# mirobot_main.net
KiCad netlist of a schematic drawn in EAGLE
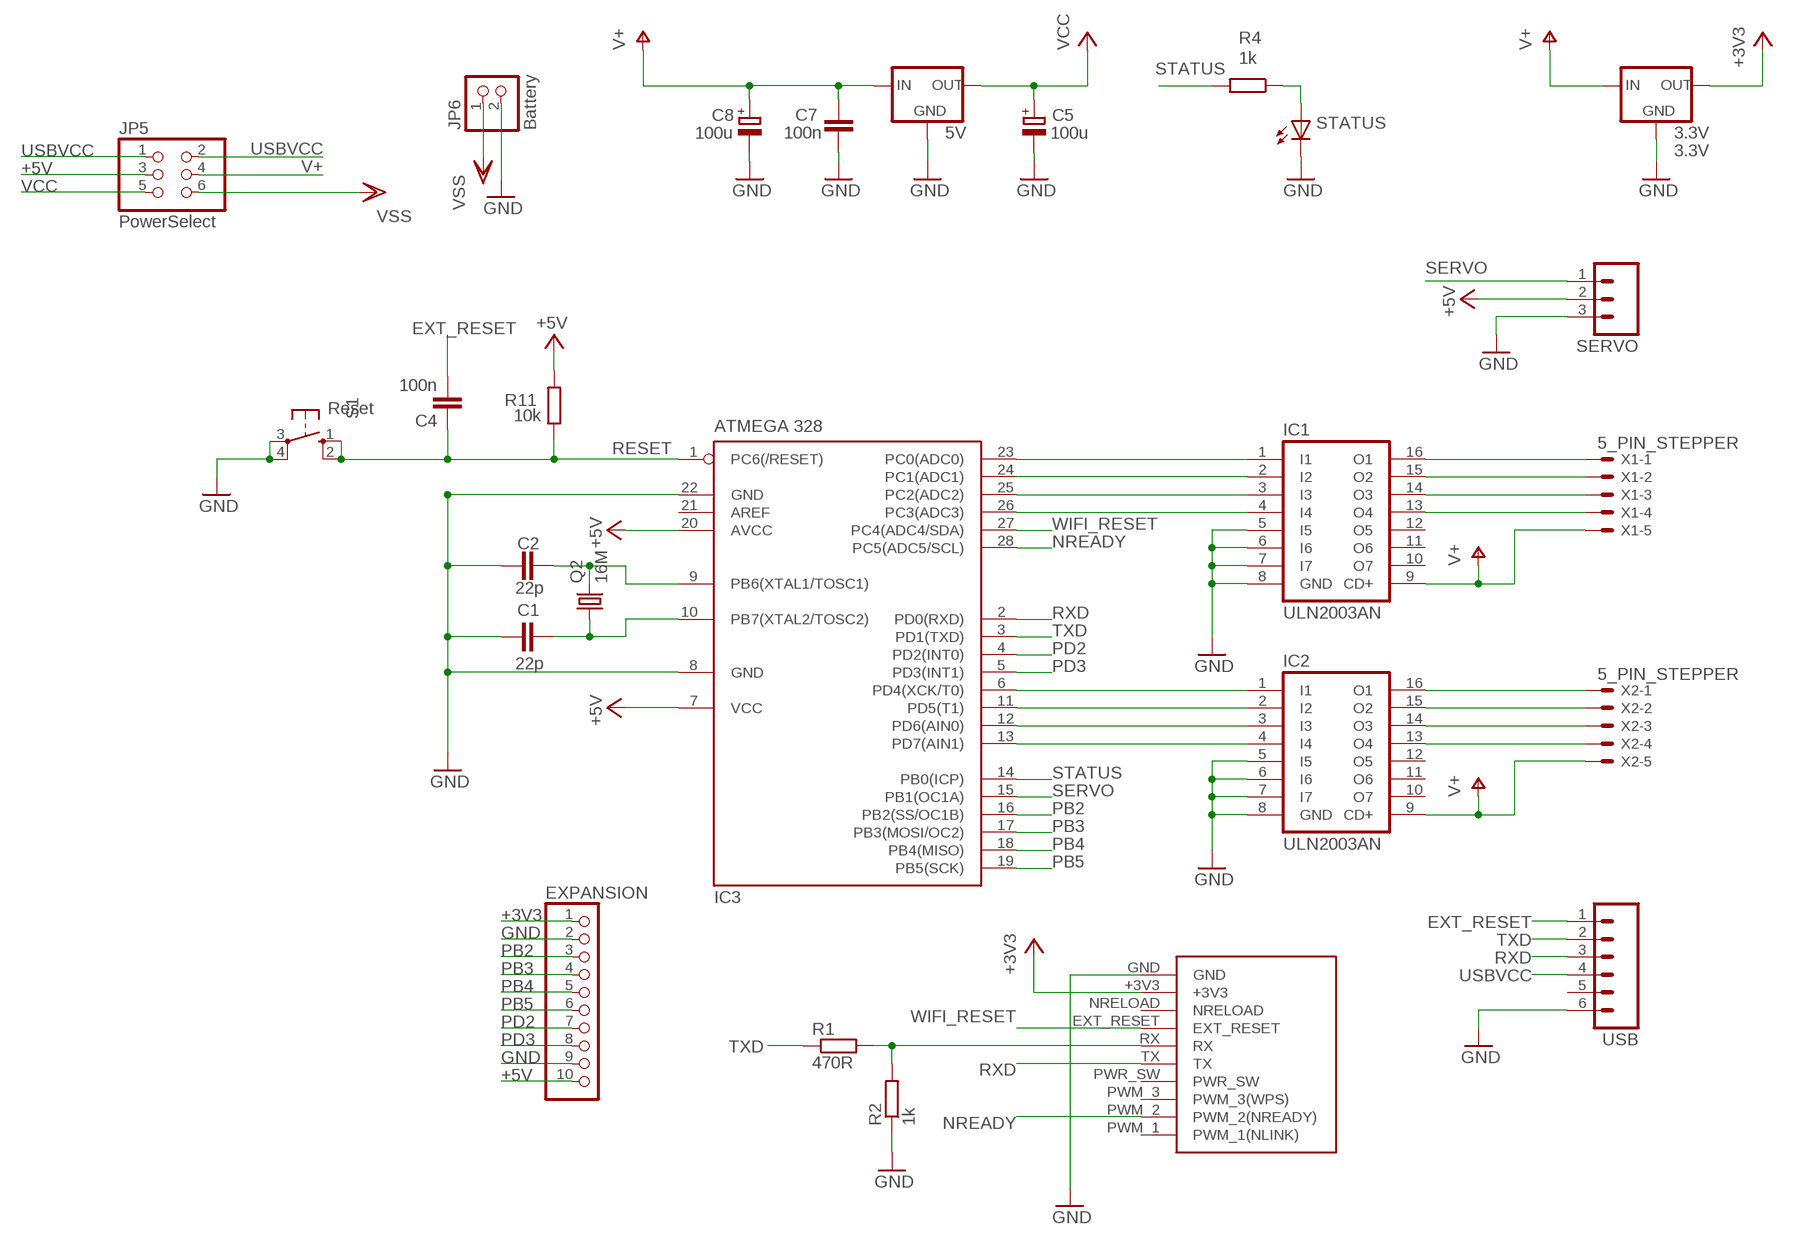
[diagram p0: schematic, sheet 1]

(export (version "E")
  (design (tool "Eeschema 10.0.6"))
  (components
    (comp (ref "3.3V")
      (value "3.3V")
      (footprint "eagle-import:78LXX")
      (libsource (lib "eagle-import") (part "78LXX"))
    )
    (comp (ref "5V")
      (value "78MXXS")
      (footprint "eagle-import:78MXXS")
      (libsource (lib "eagle-import") (part "78MXXS"))
    )
    (comp (ref "C1")
      (value "22p")
      (footprint "eagle-import:C025-024X044")
      (libsource (lib "eagle-import") (part "C-EU025-024X044"))
    )
    (comp (ref "C2")
      (value "22p")
      (footprint "eagle-import:C025-024X044")
      (libsource (lib "eagle-import") (part "C-EU025-024X044"))
    )
    (comp (ref "C4")
      (value "100n")
      (footprint "eagle-import:C050-025X075")
      (libsource (lib "eagle-import") (part "C-EU050-025X075"))
    )
    (comp (ref "C5")
      (value "100u")
      (footprint "eagle-import:E2-5")
      (libsource (lib "eagle-import") (part "CPOL-EUE2-5"))
    )
    (comp (ref "C7")
      (value "100n")
      (footprint "eagle-import:C050-025X075")
      (libsource (lib "eagle-import") (part "C-EU050-025X075"))
    )
    (comp (ref "C8")
      (value "100u")
      (footprint "eagle-import:E2-5")
      (libsource (lib "eagle-import") (part "CPOL-EUE2-5"))
    )
    (comp (ref "EXPANSION")
      (value "PINHD-1X10")
      (footprint "eagle-import:1X10")
      (libsource (lib "eagle-import") (part "PINHD-1X10"))
    )
    (comp (ref "IC1")
      (value "ULN2003AN")
      (footprint "eagle-import:DIL16")
      (libsource (lib "eagle-import") (part "ULN2003AN"))
    )
    (comp (ref "IC2")
      (value "ULN2003AN")
      (footprint "eagle-import:DIL16")
      (libsource (lib "eagle-import") (part "ULN2003AN"))
    )
    (comp (ref "IC3")
      (value "ATMEGA 328")
      (footprint "eagle-import:DIL28-3")
      (libsource (lib "eagle-import") (part "MEGA8-P"))
    )
    (comp (ref "JP5")
      (value "PowerSelect")
      (footprint "eagle-import:2X03")
      (libsource (lib "eagle-import") (part "PINHD-2X3"))
    )
    (comp (ref "JP6")
      (value "Battery")
      (footprint "eagle-import:1X02")
      (libsource (lib "eagle-import") (part "PINHD-1X2"))
    )
    (comp (ref "Q2")
      (value "16M")
      (footprint "eagle-import:HC49_S")
      (libsource (lib "eagle-import") (part "CRYSTALHC49S"))
    )
    (comp (ref "R1")
      (value "470R")
      (footprint "eagle-import:0204_5")
      (libsource (lib "eagle-import") (part "R-EU_0204/5"))
    )
    (comp (ref "R2")
      (value "1k")
      (footprint "eagle-import:0204_5")
      (libsource (lib "eagle-import") (part "R-EU_0204/5"))
    )
    (comp (ref "R4")
      (value "1k")
      (footprint "eagle-import:0204_5")
      (libsource (lib "eagle-import") (part "R-EU_0204/5"))
    )
    (comp (ref "R11")
      (value "10k")
      (footprint "eagle-import:0204_5")
      (libsource (lib "eagle-import") (part "R-EU_0204/5"))
    )
    (comp (ref "S1")
      (value "Reset")
      (footprint "eagle-import:B3F-10XX")
      (fields (field (name "MPN") "B3F-1000"))
      (libsource (lib "eagle-import") (part "10-XX"))
    )
    (comp (ref "SERVO")
      (value "M03LOCK_LONGPADS")
      (footprint "eagle-import:1X03_LOCK_LONGPADS")
      (libsource (lib "eagle-import") (part "M03LOCK_LONGPADS"))
    )
    (comp (ref "STATUS")
      (value "LED3MM")
      (footprint "eagle-import:LED3MM")
      (libsource (lib "eagle-import") (part "LED3MM"))
    )
    (comp (ref "U$1")
      (value "USR_WIFI-T")
      (footprint "eagle-import:WIFI_MODULE-T")
      (libsource (lib "eagle-import") (part "USR_WIFI-T"))
    )
    (comp (ref "USB")
      (value "M06LOCK_LONGPADS")
      (footprint "eagle-import:1X06_LOCK_LONGPADS")
      (libsource (lib "eagle-import") (part "M06LOCK_LONGPADS"))
    )
    (comp (ref "X1")
      (value "5_PIN_STEPPER")
      (footprint "eagle-import:5_PIN_STEPPER")
      (fields (field (name "MF") "MOLEX") (field (name "MPN") "22-23-2051"))
      (libsource (lib "eagle-import") (part "5_PIN_STEPPER"))
    )
    (comp (ref "X2")
      (value "5_PIN_STEPPER")
      (footprint "eagle-import:5_PIN_STEPPER")
      (fields (field (name "MF") "MOLEX") (field (name "MPN") "22-23-2051"))
      (libsource (lib "eagle-import") (part "5_PIN_STEPPER"))
    )
  )
  (nets
    (net (code "1") (name "+3V3") (class "Default")
      (node (ref "3.3V") (pin "OUT") (pinfunction "OUT_OUT") (pintype "passive"))
      (node (ref "EXPANSION") (pin "1") (pinfunction "1_1") (pintype "passive"))
      (node (ref "U$1") (pin "+3V3") (pinfunction "+3V3_+3V3") (pintype "power_in"))
    )
    (net (code "2") (name "+5V") (class "Default")
      (node (ref "EXPANSION") (pin "10") (pinfunction "10_10") (pintype "passive"))
      (node (ref "IC3") (pin "20") (pinfunction "AVCC_20") (pintype "power_in"))
      (node (ref "IC3") (pin "7") (pinfunction "VCC_7") (pintype "power_in"))
      (node (ref "JP5") (pin "3") (pinfunction "3_3") (pintype "passive"))
      (node (ref "R11") (pin "2") (pinfunction "2_2") (pintype "passive"))
      (node (ref "SERVO") (pin "2") (pinfunction "2_2") (pintype "passive"))
    )
    (net (code "3") (name "/EXT_RESET") (class "Default")
      (node (ref "C4") (pin "2") (pinfunction "2_2") (pintype "passive"))
      (node (ref "USB") (pin "1") (pinfunction "1_1") (pintype "passive"))
    )
    (net (code "4") (name "/NREADY") (class "Default")
      (node (ref "IC3") (pin "28") (pinfunction "PC5(ADC5/SCL)_28") (pintype "bidirectional"))
      (node (ref "U$1") (pin "PWM_2") (pinfunction "PWM_2(NREADY)_PWM_2") (pintype "bidirectional"))
    )
    (net (code "5") (name "/PB2") (class "Default")
      (node (ref "EXPANSION") (pin "3") (pinfunction "3_3") (pintype "passive"))
      (node (ref "IC3") (pin "16") (pinfunction "PB2(SS/OC1B)_16") (pintype "bidirectional"))
    )
    (net (code "6") (name "/PB3") (class "Default")
      (node (ref "EXPANSION") (pin "4") (pinfunction "4_4") (pintype "passive"))
      (node (ref "IC3") (pin "17") (pinfunction "PB3(MOSI/OC2)_17") (pintype "bidirectional"))
    )
    (net (code "7") (name "/PB4") (class "Default")
      (node (ref "EXPANSION") (pin "5") (pinfunction "5_5") (pintype "passive"))
      (node (ref "IC3") (pin "18") (pinfunction "PB4(MISO)_18") (pintype "bidirectional"))
    )
    (net (code "8") (name "/PB5") (class "Default")
      (node (ref "EXPANSION") (pin "6") (pinfunction "6_6") (pintype "passive"))
      (node (ref "IC3") (pin "19") (pinfunction "PB5(SCK)_19") (pintype "bidirectional"))
    )
    (net (code "9") (name "/PD2") (class "Default")
      (node (ref "EXPANSION") (pin "7") (pinfunction "7_7") (pintype "passive"))
      (node (ref "IC3") (pin "4") (pinfunction "PD2(INT0)_4") (pintype "bidirectional"))
    )
    (net (code "10") (name "/PD3") (class "Default")
      (node (ref "EXPANSION") (pin "8") (pinfunction "8_8") (pintype "passive"))
      (node (ref "IC3") (pin "5") (pinfunction "PD3(INT1)_5") (pintype "bidirectional"))
    )
    (net (code "11") (name "/RESET") (class "Default")
      (node (ref "C4") (pin "1") (pinfunction "1_1") (pintype "passive"))
      (node (ref "IC3") (pin "1") (pinfunction "PC6(/RESET)_1") (pintype "bidirectional"))
      (node (ref "R11") (pin "1") (pinfunction "1_1") (pintype "passive"))
      (node (ref "S1") (pin "1") (pinfunction "S_1") (pintype "passive"))
      (node (ref "S1") (pin "2") (pinfunction "S1_2") (pintype "passive"))
    )
    (net (code "12") (name "/RXD") (class "Default")
      (node (ref "IC3") (pin "2") (pinfunction "PD0(RXD)_2") (pintype "bidirectional"))
      (node (ref "U$1") (pin "TX") (pinfunction "TX_TX") (pintype "bidirectional"))
      (node (ref "USB") (pin "3") (pinfunction "3_3") (pintype "passive"))
    )
    (net (code "13") (name "/SERVO") (class "Default")
      (node (ref "IC3") (pin "15") (pinfunction "PB1(OC1A)_15") (pintype "bidirectional"))
      (node (ref "SERVO") (pin "1") (pinfunction "1_1") (pintype "passive"))
    )
    (net (code "14") (name "/STATUS") (class "Default")
      (node (ref "IC3") (pin "14") (pinfunction "PB0(ICP)_14") (pintype "bidirectional"))
      (node (ref "R4") (pin "2") (pinfunction "2_2") (pintype "passive"))
    )
    (net (code "15") (name "/TXD") (class "Default")
      (node (ref "IC3") (pin "3") (pinfunction "PD1(TXD)_3") (pintype "bidirectional"))
      (node (ref "R1") (pin "1") (pinfunction "1_1") (pintype "passive"))
      (node (ref "USB") (pin "2") (pinfunction "2_2") (pintype "passive"))
    )
    (net (code "16") (name "/USBVCC") (class "Default")
      (node (ref "JP5") (pin "1") (pinfunction "1_1") (pintype "passive"))
      (node (ref "JP5") (pin "2") (pinfunction "2_2") (pintype "passive"))
      (node (ref "USB") (pin "4") (pinfunction "4_4") (pintype "passive"))
    )
    (net (code "17") (name "/WIFI_RESET") (class "Default")
      (node (ref "IC3") (pin "27") (pinfunction "PC4(ADC4/SDA)_27") (pintype "bidirectional"))
      (node (ref "U$1") (pin "EXT_RESET") (pinfunction "EXT_RESET_EXT_RESET") (pintype "bidirectional"))
    )
    (net (code "18") (name "GND") (class "Default")
      (node (ref "3.3V") (pin "GND") (pinfunction "GND_GND") (pintype "input"))
      (node (ref "5V") (pin "GND") (pinfunction "GND_GND") (pintype "input"))
      (node (ref "C1") (pin "1") (pinfunction "1_1") (pintype "passive"))
      (node (ref "C2") (pin "1") (pinfunction "1_1") (pintype "passive"))
      (node (ref "C5") (pin "-") (pinfunction "-_-") (pintype "passive"))
      (node (ref "C7") (pin "1") (pinfunction "1_1") (pintype "passive"))
      (node (ref "C8") (pin "-") (pinfunction "-_-") (pintype "passive"))
      (node (ref "EXPANSION") (pin "2") (pinfunction "2_2") (pintype "passive"))
      (node (ref "EXPANSION") (pin "9") (pinfunction "9_9") (pintype "passive"))
      (node (ref "IC1") (pin "5") (pinfunction "I5_5") (pintype "input"))
      (node (ref "IC1") (pin "6") (pinfunction "I6_6") (pintype "input"))
      (node (ref "IC1") (pin "7") (pinfunction "I7_7") (pintype "input"))
      (node (ref "IC1") (pin "8") (pinfunction "GND_8") (pintype "power_in"))
      (node (ref "IC2") (pin "5") (pinfunction "I5_5") (pintype "input"))
      (node (ref "IC2") (pin "6") (pinfunction "I6_6") (pintype "input"))
      (node (ref "IC2") (pin "7") (pinfunction "I7_7") (pintype "input"))
      (node (ref "IC2") (pin "8") (pinfunction "GND_8") (pintype "power_in"))
      (node (ref "IC3") (pin "22") (pinfunction "GND_22") (pintype "power_in"))
      (node (ref "IC3") (pin "8") (pinfunction "GND_8") (pintype "power_in"))
      (node (ref "JP6") (pin "2") (pinfunction "2_2") (pintype "passive"))
      (node (ref "R2") (pin "1") (pinfunction "1_1") (pintype "passive"))
      (node (ref "S1") (pin "3") (pinfunction "P_3") (pintype "passive"))
      (node (ref "S1") (pin "4") (pinfunction "P1_4") (pintype "passive"))
      (node (ref "SERVO") (pin "3") (pinfunction "3_3") (pintype "passive"))
      (node (ref "STATUS") (pin "K") (pinfunction "C_K") (pintype "passive"))
      (node (ref "U$1") (pin "GND") (pinfunction "GND_GND") (pintype "power_in"))
      (node (ref "USB") (pin "6") (pinfunction "6_6") (pintype "passive"))
    )
    (net (code "19") (name "Net-(IC1-I1)") (class "Default")
      (node (ref "IC1") (pin "1") (pinfunction "I1_1") (pintype "input"))
      (node (ref "IC3") (pin "23") (pinfunction "PC0(ADC0)_23") (pintype "bidirectional"))
    )
    (net (code "20") (name "Net-(IC1-I2)") (class "Default")
      (node (ref "IC1") (pin "2") (pinfunction "I2_2") (pintype "input"))
      (node (ref "IC3") (pin "24") (pinfunction "PC1(ADC1)_24") (pintype "bidirectional"))
    )
    (net (code "21") (name "Net-(IC1-I3)") (class "Default")
      (node (ref "IC1") (pin "3") (pinfunction "I3_3") (pintype "input"))
      (node (ref "IC3") (pin "25") (pinfunction "PC2(ADC2)_25") (pintype "bidirectional"))
    )
    (net (code "22") (name "Net-(IC1-I4)") (class "Default")
      (node (ref "IC1") (pin "4") (pinfunction "I4_4") (pintype "input"))
      (node (ref "IC3") (pin "26") (pinfunction "PC3(ADC3)_26") (pintype "bidirectional"))
    )
    (net (code "23") (name "Net-(IC1-O1)") (class "Default")
      (node (ref "IC1") (pin "16") (pinfunction "O1_16") (pintype "open_collector"))
      (node (ref "X1") (pin "1") (pinfunction "S_1") (pintype "passive"))
    )
    (net (code "24") (name "Net-(IC1-O2)") (class "Default")
      (node (ref "IC1") (pin "15") (pinfunction "O2_15") (pintype "open_collector"))
      (node (ref "X1") (pin "2") (pinfunction "S_2") (pintype "passive"))
    )
    (net (code "25") (name "Net-(IC1-O3)") (class "Default")
      (node (ref "IC1") (pin "14") (pinfunction "O3_14") (pintype "open_collector"))
      (node (ref "X1") (pin "3") (pinfunction "S_3") (pintype "passive"))
    )
    (net (code "26") (name "Net-(IC1-O4)") (class "Default")
      (node (ref "IC1") (pin "13") (pinfunction "O4_13") (pintype "open_collector"))
      (node (ref "X1") (pin "4") (pinfunction "S_4") (pintype "passive"))
    )
    (net (code "27") (name "Net-(IC2-I1)") (class "Default")
      (node (ref "IC2") (pin "1") (pinfunction "I1_1") (pintype "input"))
      (node (ref "IC3") (pin "6") (pinfunction "PD4(XCK/T0)_6") (pintype "bidirectional"))
    )
    (net (code "28") (name "Net-(IC2-I2)") (class "Default")
      (node (ref "IC2") (pin "2") (pinfunction "I2_2") (pintype "input"))
      (node (ref "IC3") (pin "11") (pinfunction "PD5(T1)_11") (pintype "bidirectional"))
    )
    (net (code "29") (name "Net-(IC2-I3)") (class "Default")
      (node (ref "IC2") (pin "3") (pinfunction "I3_3") (pintype "input"))
      (node (ref "IC3") (pin "12") (pinfunction "PD6(AIN0)_12") (pintype "bidirectional"))
    )
    (net (code "30") (name "Net-(IC2-I4)") (class "Default")
      (node (ref "IC2") (pin "4") (pinfunction "I4_4") (pintype "input"))
      (node (ref "IC3") (pin "13") (pinfunction "PD7(AIN1)_13") (pintype "bidirectional"))
    )
    (net (code "31") (name "Net-(IC2-O1)") (class "Default")
      (node (ref "IC2") (pin "16") (pinfunction "O1_16") (pintype "open_collector"))
      (node (ref "X2") (pin "1") (pinfunction "S_1") (pintype "passive"))
    )
    (net (code "32") (name "Net-(IC2-O2)") (class "Default")
      (node (ref "IC2") (pin "15") (pinfunction "O2_15") (pintype "open_collector"))
      (node (ref "X2") (pin "2") (pinfunction "S_2") (pintype "passive"))
    )
    (net (code "33") (name "Net-(IC2-O3)") (class "Default")
      (node (ref "IC2") (pin "14") (pinfunction "O3_14") (pintype "open_collector"))
      (node (ref "X2") (pin "3") (pinfunction "S_3") (pintype "passive"))
    )
    (net (code "34") (name "Net-(IC2-O4)") (class "Default")
      (node (ref "IC2") (pin "13") (pinfunction "O4_13") (pintype "open_collector"))
      (node (ref "X2") (pin "4") (pinfunction "S_4") (pintype "passive"))
    )
    (net (code "35") (name "Net-(IC3-PB6(XTAL1{slash}TOSC1))") (class "Default")
      (node (ref "C2") (pin "2") (pinfunction "2_2") (pintype "passive"))
      (node (ref "IC3") (pin "9") (pinfunction "PB6(XTAL1/TOSC1)_9") (pintype "bidirectional"))
      (node (ref "Q2") (pin "2") (pinfunction "2_2") (pintype "passive"))
    )
    (net (code "36") (name "Net-(IC3-PB7(XTAL2{slash}TOSC2))") (class "Default")
      (node (ref "C1") (pin "2") (pinfunction "2_2") (pintype "passive"))
      (node (ref "IC3") (pin "10") (pinfunction "PB7(XTAL2/TOSC2)_10") (pintype "bidirectional"))
      (node (ref "Q2") (pin "1") (pinfunction "1_1") (pintype "passive"))
    )
    (net (code "37") (name "Net-(R1-Pad2)") (class "Default")
      (node (ref "R1") (pin "2") (pinfunction "2_2") (pintype "passive"))
      (node (ref "R2") (pin "2") (pinfunction "2_2") (pintype "passive"))
      (node (ref "U$1") (pin "RX") (pinfunction "RX_RX") (pintype "bidirectional"))
    )
    (net (code "38") (name "Net-(R4-Pad1)") (class "Default")
      (node (ref "R4") (pin "1") (pinfunction "1_1") (pintype "passive"))
      (node (ref "STATUS") (pin "A") (pinfunction "A_A") (pintype "passive"))
    )
    (net (code "39") (name "V+") (class "Default")
      (node (ref "3.3V") (pin "IN") (pinfunction "IN_IN") (pintype "input"))
      (node (ref "5V") (pin "IN") (pinfunction "IN_IN") (pintype "input"))
      (node (ref "C7") (pin "2") (pinfunction "2_2") (pintype "passive"))
      (node (ref "C8") (pin "+") (pinfunction "+_+") (pintype "passive"))
      (node (ref "IC1") (pin "9") (pinfunction "CD+_9") (pintype "passive"))
      (node (ref "IC2") (pin "9") (pinfunction "CD+_9") (pintype "passive"))
      (node (ref "JP5") (pin "4") (pinfunction "4_4") (pintype "passive"))
      (node (ref "X1") (pin "5") (pinfunction "S_5") (pintype "passive"))
      (node (ref "X2") (pin "5") (pinfunction "S_5") (pintype "passive"))
    )
    (net (code "40") (name "VCC") (class "Default")
      (node (ref "5V") (pin "OUT") (pinfunction "OUT_OUT") (pintype "passive"))
      (node (ref "C5") (pin "+") (pinfunction "+_+") (pintype "passive"))
      (node (ref "JP5") (pin "5") (pinfunction "5_5") (pintype "passive"))
    )
    (net (code "41") (name "VSS") (class "Default")
      (node (ref "JP5") (pin "6") (pinfunction "6_6") (pintype "passive"))
      (node (ref "JP6") (pin "1") (pinfunction "1_1") (pintype "passive"))
    )
    (net (code "42") (name "unconnected-(IC1-O5-Pad12)") (class "Default")
      (node (ref "IC1") (pin "12") (pinfunction "O5_12") (pintype "open_collector"))
    )
    (net (code "43") (name "unconnected-(IC1-O6-Pad11)") (class "Default")
      (node (ref "IC1") (pin "11") (pinfunction "O6_11") (pintype "open_collector"))
    )
    (net (code "44") (name "unconnected-(IC1-O7-Pad10)") (class "Default")
      (node (ref "IC1") (pin "10") (pinfunction "O7_10") (pintype "open_collector"))
    )
    (net (code "45") (name "unconnected-(IC2-O5-Pad12)") (class "Default")
      (node (ref "IC2") (pin "12") (pinfunction "O5_12") (pintype "open_collector"))
    )
    (net (code "46") (name "unconnected-(IC2-O6-Pad11)") (class "Default")
      (node (ref "IC2") (pin "11") (pinfunction "O6_11") (pintype "open_collector"))
    )
    (net (code "47") (name "unconnected-(IC2-O7-Pad10)") (class "Default")
      (node (ref "IC2") (pin "10") (pinfunction "O7_10") (pintype "open_collector"))
    )
    (net (code "48") (name "unconnected-(IC3-AREF-Pad21)") (class "Default")
      (node (ref "IC3") (pin "21") (pinfunction "AREF_21") (pintype "passive"))
    )
    (net (code "49") (name "unconnected-(U$1-PWM_1(NLINK)-PadPWM_1)") (class "Default")
      (node (ref "U$1") (pin "PWM_1") (pinfunction "PWM_1(NLINK)_PWM_1") (pintype "bidirectional"))
    )
    (net (code "50") (name "unconnected-(U$1-PWM_3(WPS)-PadPWM_3)") (class "Default")
      (node (ref "U$1") (pin "PWM_3") (pinfunction "PWM_3(WPS)_PWM_3") (pintype "bidirectional"))
    )
    (net (code "51") (name "unconnected-(U$1-PadNRELOAD)") (class "Default")
      (node (ref "U$1") (pin "NRELOAD") (pinfunction "NRELOAD_NRELOAD") (pintype "bidirectional"))
    )
    (net (code "52") (name "unconnected-(U$1-PadPWR_SW)") (class "Default")
      (node (ref "U$1") (pin "PWR_SW") (pinfunction "PWR_SW_PWR_SW") (pintype "bidirectional"))
    )
    (net (code "53") (name "unconnected-(USB-Pad5)") (class "Default")
      (node (ref "USB") (pin "5") (pinfunction "5_5") (pintype "passive"))
    )
  )
)
